# 1_interface.net
KiCad netlist of a schematic drawn in Altium Designer
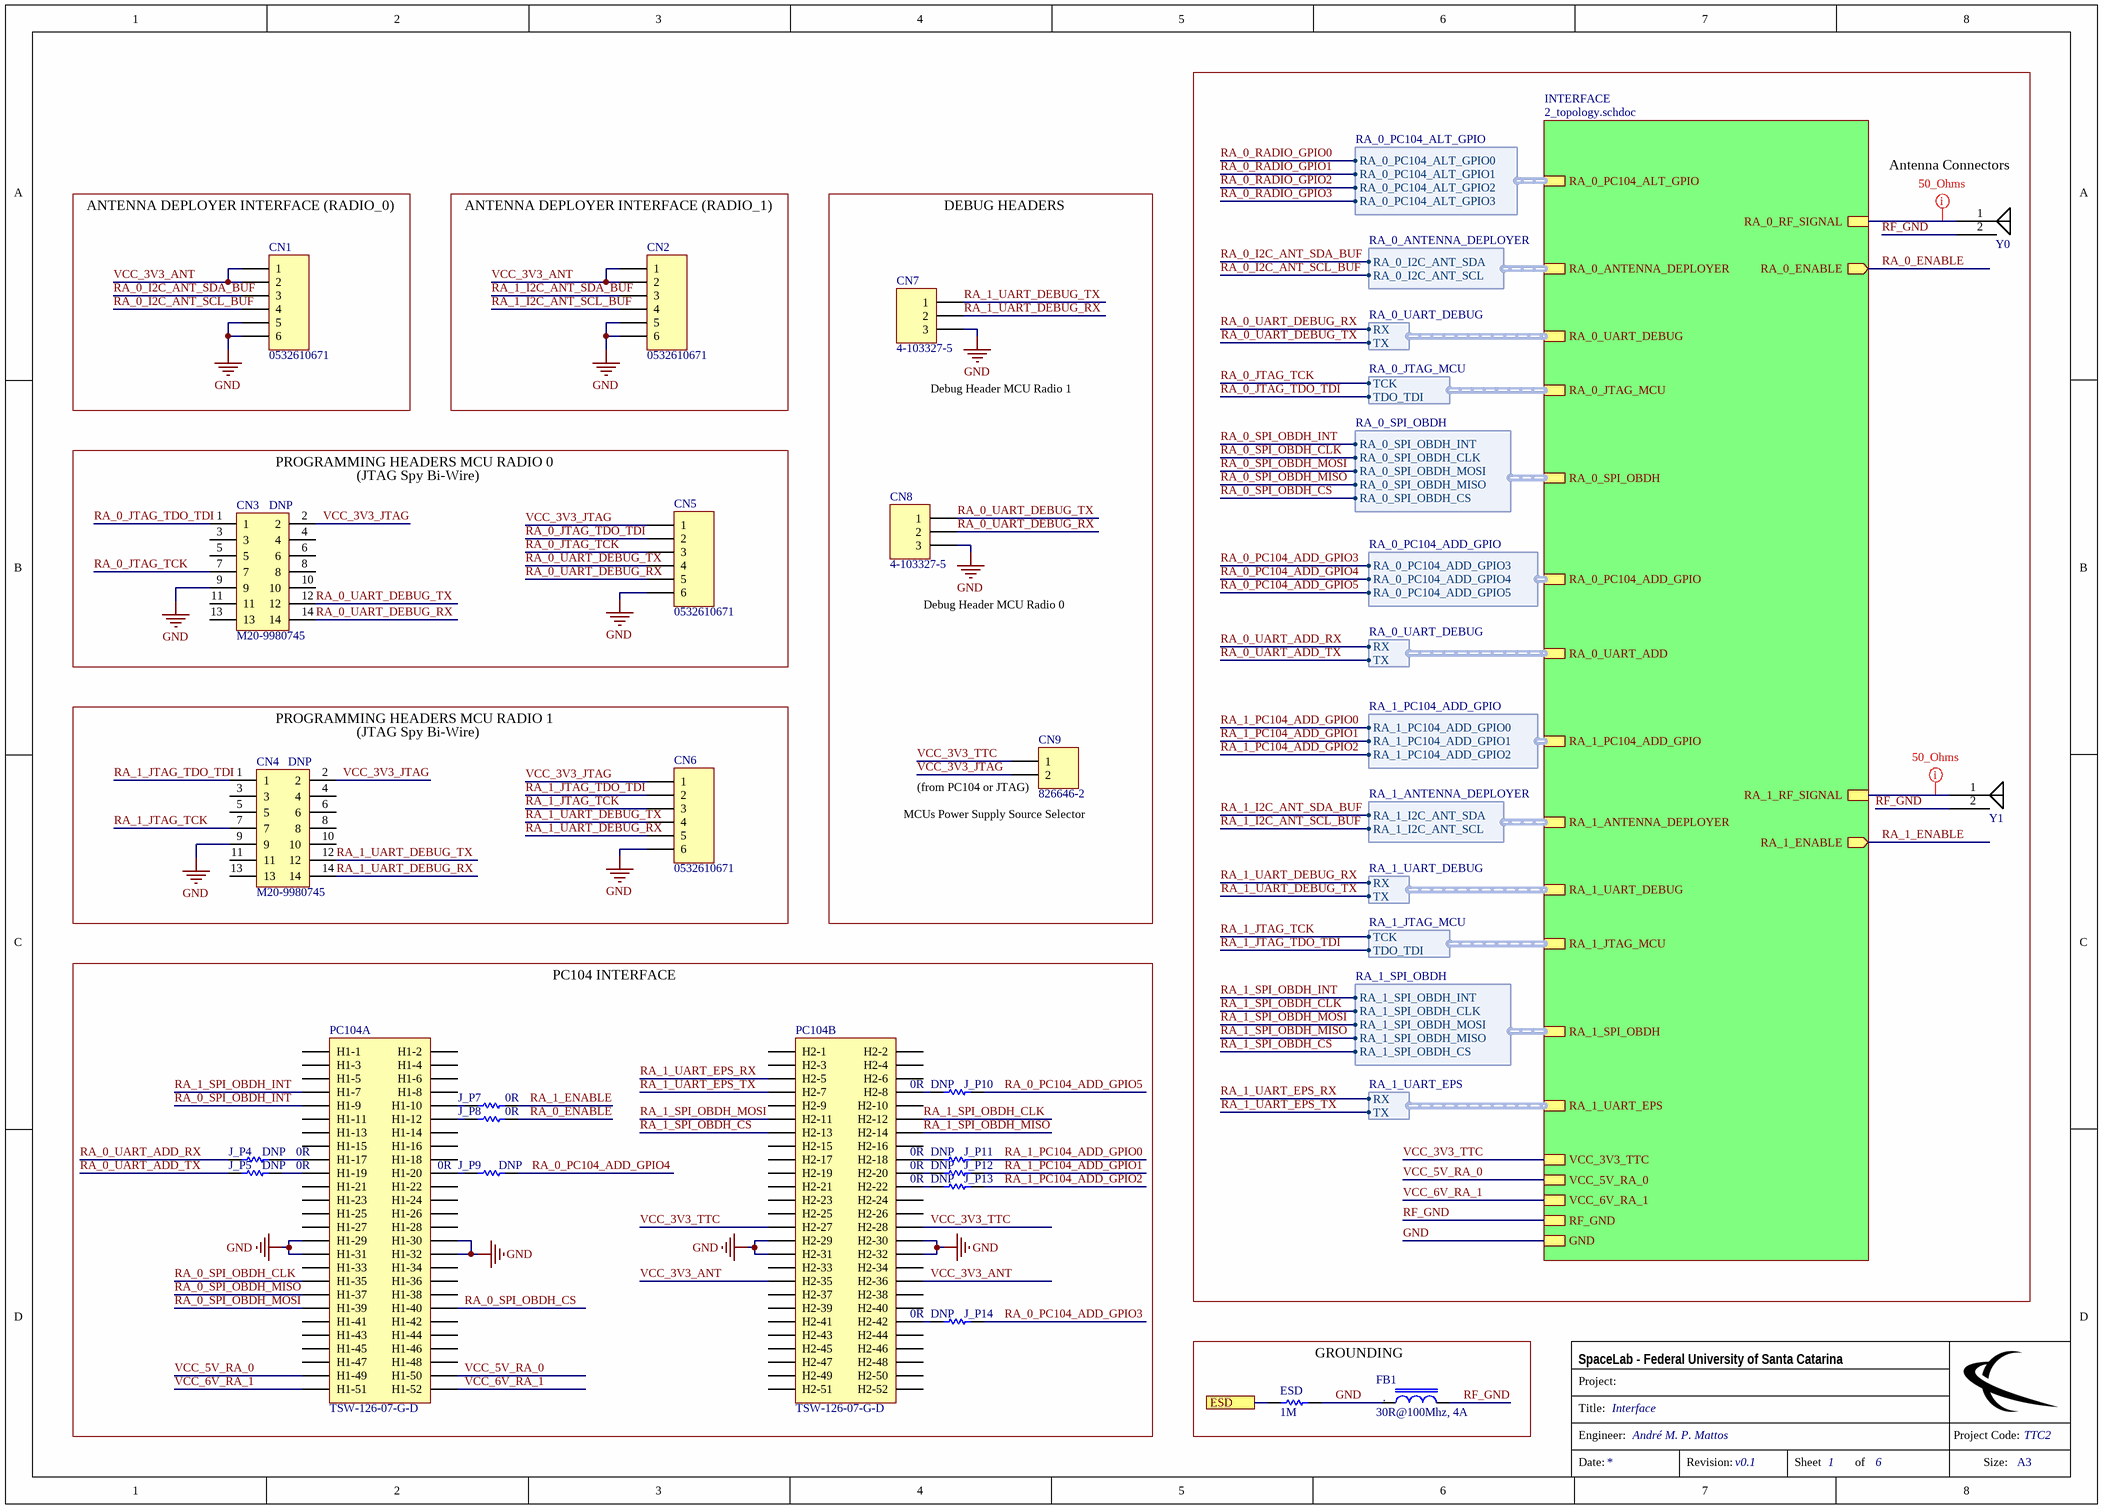
[diagram p0: 1_interface.schdoc]

(export (version "E")
  (design (tool "Eeschema 10.0.6"))
  (components
    (comp (ref "CN1")
      (value "0532610671")
      (footprint "PICOBLADE 6PIN Right Angle")
      (description "PicoBlade 6 Position Right Angle Connector Header Surface Mount  0.049\" (1.25mm)")
      (fields (field (name "PUBLISHER") "Altium Limited"))
      (libsource (lib "schematics_library_legacy") (part "0532610671"))
    )
    (comp (ref "CN2")
      (value "0532610671")
      (footprint "PICOBLADE 6PIN Right Angle")
      (description "PicoBlade 6 Position Right Angle Connector Header Surface Mount  0.049\" (1.25mm)")
      (fields (field (name "PUBLISHER") "Altium Limited"))
      (libsource (lib "schematics_library_legacy") (part "0532610671"))
    )
    (comp (ref "CN3")
      (value "M20-9980745")
      (footprint "CONN HEADER VERT 14POS 2.54MM")
      (description "Connector Header Through Hole 14 position 0.100\" (2.54mm)")
      (fields (field (name "MANUFACTURER") "Harwin"))
      (libsource (lib "schematics_library_legacy") (part "M20-9980745"))
    )
    (comp (ref "CN4")
      (value "M20-9980745")
      (footprint "CONN HEADER VERT 14POS 2.54MM")
      (description "Connector Header Through Hole 14 position 0.100\" (2.54mm)")
      (fields (field (name "MANUFACTURER") "Harwin"))
      (libsource (lib "schematics_library_legacy") (part "M20-9980745"))
    )
    (comp (ref "CN5")
      (value "0532610671")
      (footprint "PICOBLADE 6PIN Right Angle")
      (description "PicoBlade 6 Position Right Angle Connector Header Surface Mount  0.049\" (1.25mm)")
      (fields (field (name "PUBLISHER") "Altium Limited"))
      (libsource (lib "schematics_library_legacy") (part "0532610671"))
    )
    (comp (ref "CN6")
      (value "0532610671")
      (footprint "PICOBLADE 6PIN Right Angle")
      (description "PicoBlade 6 Position Right Angle Connector Header Surface Mount  0.049\" (1.25mm)")
      (fields (field (name "PUBLISHER") "Altium Limited"))
      (libsource (lib "schematics_library_legacy") (part "0532610671"))
    )
    (comp (ref "CN7")
      (value "4-103327-5")
      (footprint "HDR 1X3")
      (description "Connector Header Through Hole 3 position 0.100\" (2.54mm)")
      (fields (field (name "MANUFACTURER") "TE Connectivity AMP") (field (name "PUBLISHER") "Altium Limited"))
      (libsource (lib "schematics_library_legacy") (part "4-103327-5"))
    )
    (comp (ref "CN8")
      (value "4-103327-5")
      (footprint "HDR 1X3")
      (description "Connector Header Through Hole 3 position 0.100\" (2.54mm)")
      (fields (field (name "MANUFACTURER") "TE Connectivity AMP") (field (name "PUBLISHER") "Altium Limited"))
      (libsource (lib "schematics_library_legacy") (part "4-103327-5"))
    )
    (comp (ref "CN9")
      (value "826646-2")
      (footprint "HDR 1X2")
      (description "Connector Header Through Hole 2 position 0.100\" (2.54mm)")
      (fields (field (name "PUBLISHER") "Altium Limited"))
      (libsource (lib "schematics_library_legacy") (part "826646-2"))
    )
    (comp (ref "ESD")
      (value "1M")
      (footprint "0805")
      (description "RES 1000K OHM 1/8W 1% 0805")
      (fields (field (name "PARTNUMBER") "RMCF0805FG1M00"))
      (libsource (lib "schematics_library_legacy") (part "R1000k_1%_1/8W_0805"))
    )
    (comp (ref "FB1")
      (value "30R@100Mhz, 4A")
      (footprint "IND0805")
      (description "Ferrite Bead 30 OHM 4A 100MHz")
      (fields (field (name "PARTNUMBER") "BLM21PG300SN1D"))
      (libsource (lib "schematics_library_legacy") (part "FB_30R_4A_100MHz_0805"))
    )
    (comp (ref "J_P4")
      (value "0R")
      (footprint "0805")
      (description "RES 0R OHM 1/8W JUMPER 0805")
      (fields (field (name "PARTNUMBER") "CRCW08050000Z0EA"))
      (libsource (lib "schematics_library_legacy") (part "R0R_JUMPER_1/8W_0805"))
    )
    (comp (ref "J_P5")
      (value "0R")
      (footprint "0805")
      (description "RES 0R OHM 1/8W JUMPER 0805")
      (fields (field (name "PARTNUMBER") "CRCW08050000Z0EA"))
      (libsource (lib "schematics_library_legacy") (part "R0R_JUMPER_1/8W_0805"))
    )
    (comp (ref "J_P7")
      (value "0R")
      (footprint "0805")
      (description "RES 0R OHM 1/8W JUMPER 0805")
      (fields (field (name "PARTNUMBER") "CRCW08050000Z0EA"))
      (libsource (lib "schematics_library_legacy") (part "R0R_JUMPER_1/8W_0805"))
    )
    (comp (ref "J_P8")
      (value "0R")
      (footprint "0805")
      (description "RES 0R OHM 1/8W JUMPER 0805")
      (fields (field (name "PARTNUMBER") "CRCW08050000Z0EA"))
      (libsource (lib "schematics_library_legacy") (part "R0R_JUMPER_1/8W_0805"))
    )
    (comp (ref "J_P9")
      (value "0R")
      (footprint "0805")
      (description "RES 0R OHM 1/8W JUMPER 0805")
      (fields (field (name "PARTNUMBER") "CRCW08050000Z0EA"))
      (libsource (lib "schematics_library_legacy") (part "R0R_JUMPER_1/8W_0805"))
    )
    (comp (ref "J_P10")
      (value "0R")
      (footprint "0805")
      (description "RES 0R OHM 1/8W JUMPER 0805")
      (fields (field (name "PARTNUMBER") "CRCW08050000Z0EA"))
      (libsource (lib "schematics_library_legacy") (part "R0R_JUMPER_1/8W_0805"))
    )
    (comp (ref "J_P11")
      (value "0R")
      (footprint "0805")
      (description "RES 0R OHM 1/8W JUMPER 0805")
      (fields (field (name "PARTNUMBER") "CRCW08050000Z0EA"))
      (libsource (lib "schematics_library_legacy") (part "R0R_JUMPER_1/8W_0805"))
    )
    (comp (ref "J_P12")
      (value "0R")
      (footprint "0805")
      (description "RES 0R OHM 1/8W JUMPER 0805")
      (fields (field (name "PARTNUMBER") "CRCW08050000Z0EA"))
      (libsource (lib "schematics_library_legacy") (part "R0R_JUMPER_1/8W_0805"))
    )
    (comp (ref "J_P13")
      (value "0R")
      (footprint "0805")
      (description "RES 0R OHM 1/8W JUMPER 0805")
      (fields (field (name "PARTNUMBER") "CRCW08050000Z0EA"))
      (libsource (lib "schematics_library_legacy") (part "R0R_JUMPER_1/8W_0805"))
    )
    (comp (ref "J_P14")
      (value "0R")
      (footprint "0805")
      (description "RES 0R OHM 1/8W JUMPER 0805")
      (fields (field (name "PARTNUMBER") "CRCW08050000Z0EA"))
      (libsource (lib "schematics_library_legacy") (part "R0R_JUMPER_1/8W_0805"))
    )
    (comp (ref "PC104")
      (value "TSW-126-07-G-D")
      (footprint "PC104_TTC")
      (description "Connector Header Through Hole 52 position 0.100\" (2.54mm) - PC104 used in the TTC module")
      (fields (field (name "PARTNUMBER") "SSW-126-04-G-D"))
      (libsource (lib "schematics_library_legacy") (part "PC104_TTC"))
    )
    (comp (ref "Y0")
      (value "Coaxial_Connectors_90º")
      (footprint "CONN MCX JACK  R/A  50 OHM SMD")
      (description "MCX Connector Jack, Female Socket 50Ohm Through Hole, Right Angle Solder")
      (fields (field (name "PARTNUMBER") "133-3701-311"))
      (libsource (lib "schematics_library_legacy") (part "Coaxial_Connectors_90º"))
    )
    (comp (ref "Y1")
      (value "Coaxial_Connectors_90º")
      (footprint "CONN MCX JACK  R/A  50 OHM SMD")
      (description "MCX Connector Jack, Female Socket 50Ohm Through Hole, Right Angle Solder")
      (fields (field (name "PARTNUMBER") "133-3701-311"))
      (libsource (lib "schematics_library_legacy") (part "Coaxial_Connectors_90º"))
    )
  )
  (nets
    (net (code "13") (name "/ESD") (class "Default")
      (node (ref "ESD") (pin "2") (pinfunction "2_2") (pintype "passive"))
    )
    (net (code "14") (name "/RA_0_ENABLE") (class "Default")
      (node (ref "J_P8") (pin "1") (pinfunction "1_1") (pintype "passive"))
    )
    (net (code "15") (name "/RA_0_I2C_ANT_SCL_BUF") (class "Default")
      (node (ref "CN1") (pin "4") (pinfunction "4_4") (pintype "passive"))
    )
    (net (code "16") (name "/RA_0_I2C_ANT_SDA_BUF") (class "Default")
      (node (ref "CN1") (pin "3") (pinfunction "3_3") (pintype "passive"))
    )
    (net (code "17") (name "/RA_0_JTAG_TCK") (class "Default")
      (node (ref "CN3") (pin "7") (pinfunction "7_7") (pintype "passive"))
      (node (ref "CN5") (pin "3") (pinfunction "3_3") (pintype "passive"))
    )
    (net (code "18") (name "/RA_0_JTAG_TDO_TDI") (class "Default")
      (node (ref "CN3") (pin "1") (pinfunction "1_1") (pintype "passive"))
      (node (ref "CN5") (pin "2") (pinfunction "2_2") (pintype "passive"))
    )
    (net (code "19") (name "/RA_0_PC104_ADD_GPIO3") (class "Default")
      (node (ref "J_P14") (pin "1") (pinfunction "1_1") (pintype "passive"))
    )
    (net (code "20") (name "/RA_0_PC104_ADD_GPIO4") (class "Default")
      (node (ref "J_P9") (pin "1") (pinfunction "1_1") (pintype "passive"))
    )
    (net (code "21") (name "/RA_0_PC104_ADD_GPIO5") (class "Default")
      (node (ref "J_P10") (pin "1") (pinfunction "1_1") (pintype "passive"))
    )
    (net (code "26") (name "/RA_0_RF_SIGNAL") (class "Default")
      (node (ref "Y0") (pin "1") (pinfunction "1_1") (pintype "passive"))
    )
    (net (code "27") (name "/RA_0_SPI_OBDH_CLK") (class "Default")
      (node (ref "PC104") (pin "H1-35") (pinfunction "H1-35_H1-35") (pintype "passive"))
    )
    (net (code "28") (name "/RA_0_SPI_OBDH_CS") (class "Default")
      (node (ref "PC104") (pin "H1-40") (pinfunction "H1-40_H1-40") (pintype "passive"))
    )
    (net (code "29") (name "/RA_0_SPI_OBDH_INT") (class "Default")
      (node (ref "PC104") (pin "H1-9") (pinfunction "H1-9_H1-9") (pintype "passive"))
    )
    (net (code "30") (name "/RA_0_SPI_OBDH_MISO") (class "Default")
      (node (ref "PC104") (pin "H1-37") (pinfunction "H1-37_H1-37") (pintype "passive"))
    )
    (net (code "31") (name "/RA_0_SPI_OBDH_MOSI") (class "Default")
      (node (ref "PC104") (pin "H1-39") (pinfunction "H1-39_H1-39") (pintype "passive"))
    )
    (net (code "32") (name "/RA_0_UART_ADD_RX") (class "Default")
      (node (ref "J_P4") (pin "2") (pinfunction "2_2") (pintype "passive"))
    )
    (net (code "33") (name "/RA_0_UART_ADD_TX") (class "Default")
      (node (ref "J_P5") (pin "2") (pinfunction "2_2") (pintype "passive"))
    )
    (net (code "34") (name "/RA_0_UART_DEBUG_RX") (class "Default")
      (node (ref "CN3") (pin "14") (pinfunction "14_14") (pintype "passive"))
      (node (ref "CN5") (pin "5") (pinfunction "5_5") (pintype "passive"))
      (node (ref "CN8") (pin "2") (pinfunction "2_2") (pintype "passive"))
    )
    (net (code "35") (name "/RA_0_UART_DEBUG_TX") (class "Default")
      (node (ref "CN3") (pin "12") (pinfunction "12_12") (pintype "passive"))
      (node (ref "CN5") (pin "4") (pinfunction "4_4") (pintype "passive"))
      (node (ref "CN8") (pin "1") (pinfunction "1_1") (pintype "passive"))
    )
    (net (code "36") (name "/RA_1_ENABLE") (class "Default")
      (node (ref "J_P7") (pin "1") (pinfunction "1_1") (pintype "passive"))
    )
    (net (code "37") (name "/RA_1_I2C_ANT_SCL_BUF") (class "Default")
      (node (ref "CN2") (pin "4") (pinfunction "4_4") (pintype "passive"))
    )
    (net (code "38") (name "/RA_1_I2C_ANT_SDA_BUF") (class "Default")
      (node (ref "CN2") (pin "3") (pinfunction "3_3") (pintype "passive"))
    )
    (net (code "39") (name "/RA_1_JTAG_TCK") (class "Default")
      (node (ref "CN4") (pin "7") (pinfunction "7_7") (pintype "passive"))
      (node (ref "CN6") (pin "3") (pinfunction "3_3") (pintype "passive"))
    )
    (net (code "40") (name "/RA_1_JTAG_TDO_TDI") (class "Default")
      (node (ref "CN4") (pin "1") (pinfunction "1_1") (pintype "passive"))
      (node (ref "CN6") (pin "2") (pinfunction "2_2") (pintype "passive"))
    )
    (net (code "41") (name "/RA_1_PC104_ADD_GPIO0") (class "Default")
      (node (ref "J_P11") (pin "1") (pinfunction "1_1") (pintype "passive"))
    )
    (net (code "42") (name "/RA_1_PC104_ADD_GPIO1") (class "Default")
      (node (ref "J_P12") (pin "1") (pinfunction "1_1") (pintype "passive"))
    )
    (net (code "43") (name "/RA_1_PC104_ADD_GPIO2") (class "Default")
      (node (ref "J_P13") (pin "1") (pinfunction "1_1") (pintype "passive"))
    )
    (net (code "44") (name "/RA_1_RF_SIGNAL") (class "Default")
      (node (ref "Y1") (pin "1") (pinfunction "1_1") (pintype "passive"))
    )
    (net (code "45") (name "/RA_1_SPI_OBDH_CLK") (class "Default")
      (node (ref "PC104") (pin "H2-12") (pinfunction "H2-12_H2-12") (pintype "passive"))
    )
    (net (code "46") (name "/RA_1_SPI_OBDH_CS") (class "Default")
      (node (ref "PC104") (pin "H2-13") (pinfunction "H2-13_H2-13") (pintype "passive"))
    )
    (net (code "47") (name "/RA_1_SPI_OBDH_INT") (class "Default")
      (node (ref "PC104") (pin "H1-7") (pinfunction "H1-7_H1-7") (pintype "passive"))
    )
    (net (code "48") (name "/RA_1_SPI_OBDH_MISO") (class "Default")
      (node (ref "PC104") (pin "H2-14") (pinfunction "H2-14_H2-14") (pintype "passive"))
    )
    (net (code "49") (name "/RA_1_SPI_OBDH_MOSI") (class "Default")
      (node (ref "PC104") (pin "H2-11") (pinfunction "H2-11_H2-11") (pintype "passive"))
    )
    (net (code "50") (name "/RA_1_UART_DEBUG_RX") (class "Default")
      (node (ref "CN4") (pin "14") (pinfunction "14_14") (pintype "passive"))
      (node (ref "CN6") (pin "5") (pinfunction "5_5") (pintype "passive"))
      (node (ref "CN7") (pin "2") (pinfunction "2_2") (pintype "passive"))
    )
    (net (code "51") (name "/RA_1_UART_DEBUG_TX") (class "Default")
      (node (ref "CN4") (pin "12") (pinfunction "12_12") (pintype "passive"))
      (node (ref "CN6") (pin "4") (pinfunction "4_4") (pintype "passive"))
      (node (ref "CN7") (pin "1") (pinfunction "1_1") (pintype "passive"))
    )
    (net (code "52") (name "/RA_1_UART_EPS_RX") (class "Default")
      (node (ref "PC104") (pin "H2-5") (pinfunction "H2-5_H2-5") (pintype "passive"))
    )
    (net (code "53") (name "/RA_1_UART_EPS_TX") (class "Default")
      (node (ref "PC104") (pin "H2-7") (pinfunction "H2-7_H2-7") (pintype "passive"))
    )
    (net (code "54") (name "/RF_GND") (class "Default")
      (node (ref "FB1") (pin "2") (pinfunction "2_2") (pintype "passive"))
      (node (ref "Y0") (pin "2") (pinfunction "2_2") (pintype "passive"))
      (node (ref "Y1") (pin "2") (pinfunction "2_2") (pintype "passive"))
    )
    (net (code "55") (name "/VCC_3V3_ANT") (class "Default")
      (node (ref "CN1") (pin "1") (pinfunction "1_1") (pintype "passive"))
      (node (ref "CN1") (pin "2") (pinfunction "2_2") (pintype "passive"))
      (node (ref "CN2") (pin "1") (pinfunction "1_1") (pintype "passive"))
      (node (ref "CN2") (pin "2") (pinfunction "2_2") (pintype "passive"))
      (node (ref "PC104") (pin "H2-35") (pinfunction "H2-35_H2-35") (pintype "passive"))
      (node (ref "PC104") (pin "H2-36") (pinfunction "H2-36_H2-36") (pintype "passive"))
    )
    (net (code "56") (name "/VCC_3V3_JTAG") (class "Default")
      (node (ref "CN3") (pin "2") (pinfunction "2_2") (pintype "passive"))
      (node (ref "CN4") (pin "2") (pinfunction "2_2") (pintype "passive"))
      (node (ref "CN5") (pin "1") (pinfunction "1_1") (pintype "passive"))
      (node (ref "CN6") (pin "1") (pinfunction "1_1") (pintype "passive"))
      (node (ref "CN9") (pin "2") (pinfunction "2_2") (pintype "passive"))
    )
    (net (code "57") (name "/VCC_3V3_TTC") (class "Default")
      (node (ref "CN9") (pin "1") (pinfunction "1_1") (pintype "passive"))
      (node (ref "PC104") (pin "H2-27") (pinfunction "H2-27_H2-27") (pintype "passive"))
      (node (ref "PC104") (pin "H2-28") (pinfunction "H2-28_H2-28") (pintype "passive"))
    )
    (net (code "58") (name "/VCC_5V_RA_0") (class "Default")
      (node (ref "PC104") (pin "H1-49") (pinfunction "H1-49_H1-49") (pintype "passive"))
      (node (ref "PC104") (pin "H1-50") (pinfunction "H1-50_H1-50") (pintype "passive"))
    )
    (net (code "59") (name "/VCC_6V_RA_1") (class "Default")
      (node (ref "PC104") (pin "H1-51") (pinfunction "H1-51_H1-51") (pintype "passive"))
      (node (ref "PC104") (pin "H1-52") (pinfunction "H1-52_H1-52") (pintype "passive"))
    )
    (net (code "72") (name "GND") (class "Default")
      (node (ref "CN1") (pin "5") (pinfunction "5_5") (pintype "passive"))
      (node (ref "CN1") (pin "6") (pinfunction "6_6") (pintype "passive"))
      (node (ref "CN2") (pin "5") (pinfunction "5_5") (pintype "passive"))
      (node (ref "CN2") (pin "6") (pinfunction "6_6") (pintype "passive"))
      (node (ref "CN3") (pin "9") (pinfunction "9_9") (pintype "passive"))
      (node (ref "CN4") (pin "9") (pinfunction "9_9") (pintype "passive"))
      (node (ref "CN5") (pin "6") (pinfunction "6_6") (pintype "passive"))
      (node (ref "CN6") (pin "6") (pinfunction "6_6") (pintype "passive"))
      (node (ref "CN7") (pin "3") (pinfunction "3_3") (pintype "passive"))
      (node (ref "CN8") (pin "3") (pinfunction "3_3") (pintype "passive"))
      (node (ref "ESD") (pin "1") (pinfunction "1_1") (pintype "passive"))
      (node (ref "FB1") (pin "1") (pinfunction "1_1") (pintype "passive"))
      (node (ref "PC104") (pin "H1-29") (pinfunction "H1-29_H1-29") (pintype "passive"))
      (node (ref "PC104") (pin "H1-30") (pinfunction "H1-30_H1-30") (pintype "passive"))
      (node (ref "PC104") (pin "H1-31") (pinfunction "H1-31_H1-31") (pintype "passive"))
      (node (ref "PC104") (pin "H1-32") (pinfunction "H1-32_H1-32") (pintype "passive"))
      (node (ref "PC104") (pin "H2-29") (pinfunction "H2-29_H2-29") (pintype "passive"))
      (node (ref "PC104") (pin "H2-30") (pinfunction "H2-30_H2-30") (pintype "passive"))
      (node (ref "PC104") (pin "H2-31") (pinfunction "H2-31_H2-31") (pintype "passive"))
      (node (ref "PC104") (pin "H2-32") (pinfunction "H2-32_H2-32") (pintype "passive"))
    )
    (net (code "73") (name "Net-(J_P4-Pad1)") (class "Default")
      (node (ref "J_P4") (pin "1") (pinfunction "1_1") (pintype "passive"))
      (node (ref "PC104") (pin "H1-17") (pinfunction "H1-17_H1-17") (pintype "passive"))
    )
    (net (code "74") (name "Net-(J_P5-Pad1)") (class "Default")
      (node (ref "J_P5") (pin "1") (pinfunction "1_1") (pintype "passive"))
      (node (ref "PC104") (pin "H1-19") (pinfunction "H1-19_H1-19") (pintype "passive"))
    )
    (net (code "75") (name "Net-(J_P7-Pad2)") (class "Default")
      (node (ref "J_P7") (pin "2") (pinfunction "2_2") (pintype "passive"))
      (node (ref "PC104") (pin "H1-10") (pinfunction "H1-10_H1-10") (pintype "passive"))
    )
    (net (code "76") (name "Net-(J_P8-Pad2)") (class "Default")
      (node (ref "J_P8") (pin "2") (pinfunction "2_2") (pintype "passive"))
      (node (ref "PC104") (pin "H1-12") (pinfunction "H1-12_H1-12") (pintype "passive"))
    )
    (net (code "77") (name "Net-(J_P9-Pad2)") (class "Default")
      (node (ref "J_P9") (pin "2") (pinfunction "2_2") (pintype "passive"))
      (node (ref "PC104") (pin "H1-20") (pinfunction "H1-20_H1-20") (pintype "passive"))
    )
    (net (code "78") (name "Net-(J_P10-Pad2)") (class "Default")
      (node (ref "J_P10") (pin "2") (pinfunction "2_2") (pintype "passive"))
      (node (ref "PC104") (pin "H2-8") (pinfunction "H2-8_H2-8") (pintype "passive"))
    )
    (net (code "79") (name "Net-(J_P11-Pad2)") (class "Default")
      (node (ref "J_P11") (pin "2") (pinfunction "2_2") (pintype "passive"))
      (node (ref "PC104") (pin "H2-18") (pinfunction "H2-18_H2-18") (pintype "passive"))
    )
    (net (code "80") (name "Net-(J_P12-Pad2)") (class "Default")
      (node (ref "J_P12") (pin "2") (pinfunction "2_2") (pintype "passive"))
      (node (ref "PC104") (pin "H2-20") (pinfunction "H2-20_H2-20") (pintype "passive"))
    )
    (net (code "81") (name "Net-(J_P13-Pad2)") (class "Default")
      (node (ref "J_P13") (pin "2") (pinfunction "2_2") (pintype "passive"))
      (node (ref "PC104") (pin "H2-22") (pinfunction "H2-22_H2-22") (pintype "passive"))
    )
    (net (code "82") (name "Net-(J_P14-Pad2)") (class "Default")
      (node (ref "J_P14") (pin "2") (pinfunction "2_2") (pintype "passive"))
      (node (ref "PC104") (pin "H2-42") (pinfunction "H2-42_H2-42") (pintype "passive"))
    )
    (net (code "83") (name "unconnected-(CN3-Pad3)") (class "Default")
      (node (ref "CN3") (pin "3") (pinfunction "3_3") (pintype "passive"))
    )
    (net (code "84") (name "unconnected-(CN3-Pad4)") (class "Default")
      (node (ref "CN3") (pin "4") (pinfunction "4_4") (pintype "passive"))
    )
    (net (code "85") (name "unconnected-(CN3-Pad5)") (class "Default")
      (node (ref "CN3") (pin "5") (pinfunction "5_5") (pintype "passive"))
    )
    (net (code "86") (name "unconnected-(CN3-Pad6)") (class "Default")
      (node (ref "CN3") (pin "6") (pinfunction "6_6") (pintype "passive"))
    )
    (net (code "87") (name "unconnected-(CN3-Pad8)") (class "Default")
      (node (ref "CN3") (pin "8") (pinfunction "8_8") (pintype "passive"))
    )
    (net (code "88") (name "unconnected-(CN3-Pad10)") (class "Default")
      (node (ref "CN3") (pin "10") (pinfunction "10_10") (pintype "passive"))
    )
    (net (code "89") (name "unconnected-(CN3-Pad11)") (class "Default")
      (node (ref "CN3") (pin "11") (pinfunction "11_11") (pintype "passive"))
    )
    (net (code "90") (name "unconnected-(CN3-Pad13)") (class "Default")
      (node (ref "CN3") (pin "13") (pinfunction "13_13") (pintype "passive"))
    )
    (net (code "91") (name "unconnected-(CN4-Pad3)") (class "Default")
      (node (ref "CN4") (pin "3") (pinfunction "3_3") (pintype "passive"))
    )
    (net (code "92") (name "unconnected-(CN4-Pad4)") (class "Default")
      (node (ref "CN4") (pin "4") (pinfunction "4_4") (pintype "passive"))
    )
    (net (code "93") (name "unconnected-(CN4-Pad5)") (class "Default")
      (node (ref "CN4") (pin "5") (pinfunction "5_5") (pintype "passive"))
    )
    (net (code "94") (name "unconnected-(CN4-Pad6)") (class "Default")
      (node (ref "CN4") (pin "6") (pinfunction "6_6") (pintype "passive"))
    )
    (net (code "95") (name "unconnected-(CN4-Pad8)") (class "Default")
      (node (ref "CN4") (pin "8") (pinfunction "8_8") (pintype "passive"))
    )
    (net (code "96") (name "unconnected-(CN4-Pad10)") (class "Default")
      (node (ref "CN4") (pin "10") (pinfunction "10_10") (pintype "passive"))
    )
    (net (code "97") (name "unconnected-(CN4-Pad11)") (class "Default")
      (node (ref "CN4") (pin "11") (pinfunction "11_11") (pintype "passive"))
    )
    (net (code "98") (name "unconnected-(CN4-Pad13)") (class "Default")
      (node (ref "CN4") (pin "13") (pinfunction "13_13") (pintype "passive"))
    )
    (net (code "99") (name "unconnected-(PC104-PadH1-1)") (class "Default")
      (node (ref "PC104") (pin "H1-1") (pinfunction "H1-1_H1-1") (pintype "passive"))
    )
    (net (code "100") (name "unconnected-(PC104-PadH1-2)") (class "Default")
      (node (ref "PC104") (pin "H1-2") (pinfunction "H1-2_H1-2") (pintype "passive"))
    )
    (net (code "101") (name "unconnected-(PC104-PadH1-3)") (class "Default")
      (node (ref "PC104") (pin "H1-3") (pinfunction "H1-3_H1-3") (pintype "passive"))
    )
    (net (code "102") (name "unconnected-(PC104-PadH1-4)") (class "Default")
      (node (ref "PC104") (pin "H1-4") (pinfunction "H1-4_H1-4") (pintype "passive"))
    )
    (net (code "103") (name "unconnected-(PC104-PadH1-5)") (class "Default")
      (node (ref "PC104") (pin "H1-5") (pinfunction "H1-5_H1-5") (pintype "passive"))
    )
    (net (code "104") (name "unconnected-(PC104-PadH1-6)") (class "Default")
      (node (ref "PC104") (pin "H1-6") (pinfunction "H1-6_H1-6") (pintype "passive"))
    )
    (net (code "105") (name "unconnected-(PC104-PadH1-8)") (class "Default")
      (node (ref "PC104") (pin "H1-8") (pinfunction "H1-8_H1-8") (pintype "passive"))
    )
    (net (code "106") (name "unconnected-(PC104-PadH1-11)") (class "Default")
      (node (ref "PC104") (pin "H1-11") (pinfunction "H1-11_H1-11") (pintype "passive"))
    )
    (net (code "107") (name "unconnected-(PC104-PadH1-13)") (class "Default")
      (node (ref "PC104") (pin "H1-13") (pinfunction "H1-13_H1-13") (pintype "passive"))
    )
    (net (code "108") (name "unconnected-(PC104-PadH1-14)") (class "Default")
      (node (ref "PC104") (pin "H1-14") (pinfunction "H1-14_H1-14") (pintype "passive"))
    )
    (net (code "109") (name "unconnected-(PC104-PadH1-15)") (class "Default")
      (node (ref "PC104") (pin "H1-15") (pinfunction "H1-15_H1-15") (pintype "passive"))
    )
    (net (code "110") (name "unconnected-(PC104-PadH1-16)") (class "Default")
      (node (ref "PC104") (pin "H1-16") (pinfunction "H1-16_H1-16") (pintype "passive"))
    )
    (net (code "111") (name "unconnected-(PC104-PadH1-18)") (class "Default")
      (node (ref "PC104") (pin "H1-18") (pinfunction "H1-18_H1-18") (pintype "passive"))
    )
    (net (code "112") (name "unconnected-(PC104-PadH1-21)") (class "Default")
      (node (ref "PC104") (pin "H1-21") (pinfunction "H1-21_H1-21") (pintype "passive"))
    )
    (net (code "113") (name "unconnected-(PC104-PadH1-22)") (class "Default")
      (node (ref "PC104") (pin "H1-22") (pinfunction "H1-22_H1-22") (pintype "passive"))
    )
    (net (code "114") (name "unconnected-(PC104-PadH1-23)") (class "Default")
      (node (ref "PC104") (pin "H1-23") (pinfunction "H1-23_H1-23") (pintype "passive"))
    )
    (net (code "115") (name "unconnected-(PC104-PadH1-24)") (class "Default")
      (node (ref "PC104") (pin "H1-24") (pinfunction "H1-24_H1-24") (pintype "passive"))
    )
    (net (code "116") (name "unconnected-(PC104-PadH1-25)") (class "Default")
      (node (ref "PC104") (pin "H1-25") (pinfunction "H1-25_H1-25") (pintype "passive"))
    )
    (net (code "117") (name "unconnected-(PC104-PadH1-26)") (class "Default")
      (node (ref "PC104") (pin "H1-26") (pinfunction "H1-26_H1-26") (pintype "passive"))
    )
    (net (code "118") (name "unconnected-(PC104-PadH1-27)") (class "Default")
      (node (ref "PC104") (pin "H1-27") (pinfunction "H1-27_H1-27") (pintype "passive"))
    )
    (net (code "119") (name "unconnected-(PC104-PadH1-28)") (class "Default")
      (node (ref "PC104") (pin "H1-28") (pinfunction "H1-28_H1-28") (pintype "passive"))
    )
    (net (code "120") (name "unconnected-(PC104-PadH1-33)") (class "Default")
      (node (ref "PC104") (pin "H1-33") (pinfunction "H1-33_H1-33") (pintype "passive"))
    )
    (net (code "121") (name "unconnected-(PC104-PadH1-34)") (class "Default")
      (node (ref "PC104") (pin "H1-34") (pinfunction "H1-34_H1-34") (pintype "passive"))
    )
    (net (code "122") (name "unconnected-(PC104-PadH1-36)") (class "Default")
      (node (ref "PC104") (pin "H1-36") (pinfunction "H1-36_H1-36") (pintype "passive"))
    )
    (net (code "123") (name "unconnected-(PC104-PadH1-38)") (class "Default")
      (node (ref "PC104") (pin "H1-38") (pinfunction "H1-38_H1-38") (pintype "passive"))
    )
    (net (code "124") (name "unconnected-(PC104-PadH1-41)") (class "Default")
      (node (ref "PC104") (pin "H1-41") (pinfunction "H1-41_H1-41") (pintype "passive"))
    )
    (net (code "125") (name "unconnected-(PC104-PadH1-42)") (class "Default")
      (node (ref "PC104") (pin "H1-42") (pinfunction "H1-42_H1-42") (pintype "passive"))
    )
    (net (code "126") (name "unconnected-(PC104-PadH1-43)") (class "Default")
      (node (ref "PC104") (pin "H1-43") (pinfunction "H1-43_H1-43") (pintype "passive"))
    )
    (net (code "127") (name "unconnected-(PC104-PadH1-44)") (class "Default")
      (node (ref "PC104") (pin "H1-44") (pinfunction "H1-44_H1-44") (pintype "passive"))
    )
    (net (code "128") (name "unconnected-(PC104-PadH1-45)") (class "Default")
      (node (ref "PC104") (pin "H1-45") (pinfunction "H1-45_H1-45") (pintype "passive"))
    )
    (net (code "129") (name "unconnected-(PC104-PadH1-46)") (class "Default")
      (node (ref "PC104") (pin "H1-46") (pinfunction "H1-46_H1-46") (pintype "passive"))
    )
    (net (code "130") (name "unconnected-(PC104-PadH1-47)") (class "Default")
      (node (ref "PC104") (pin "H1-47") (pinfunction "H1-47_H1-47") (pintype "passive"))
    )
    (net (code "131") (name "unconnected-(PC104-PadH1-48)") (class "Default")
      (node (ref "PC104") (pin "H1-48") (pinfunction "H1-48_H1-48") (pintype "passive"))
    )
    (net (code "132") (name "unconnected-(PC104-PadH2-1)") (class "Default")
      (node (ref "PC104") (pin "H2-1") (pinfunction "H2-1_H2-1") (pintype "passive"))
    )
    (net (code "133") (name "unconnected-(PC104-PadH2-2)") (class "Default")
      (node (ref "PC104") (pin "H2-2") (pinfunction "H2-2_H2-2") (pintype "passive"))
    )
    (net (code "134") (name "unconnected-(PC104-PadH2-3)") (class "Default")
      (node (ref "PC104") (pin "H2-3") (pinfunction "H2-3_H2-3") (pintype "passive"))
    )
    (net (code "135") (name "unconnected-(PC104-PadH2-4)") (class "Default")
      (node (ref "PC104") (pin "H2-4") (pinfunction "H2-4_H2-4") (pintype "passive"))
    )
    (net (code "136") (name "unconnected-(PC104-PadH2-6)") (class "Default")
      (node (ref "PC104") (pin "H2-6") (pinfunction "H2-6_H2-6") (pintype "passive"))
    )
    (net (code "137") (name "unconnected-(PC104-PadH2-9)") (class "Default")
      (node (ref "PC104") (pin "H2-9") (pinfunction "H2-9_H2-9") (pintype "passive"))
    )
    (net (code "138") (name "unconnected-(PC104-PadH2-10)") (class "Default")
      (node (ref "PC104") (pin "H2-10") (pinfunction "H2-10_H2-10") (pintype "passive"))
    )
    (net (code "139") (name "unconnected-(PC104-PadH2-15)") (class "Default")
      (node (ref "PC104") (pin "H2-15") (pinfunction "H2-15_H2-15") (pintype "passive"))
    )
    (net (code "140") (name "unconnected-(PC104-PadH2-16)") (class "Default")
      (node (ref "PC104") (pin "H2-16") (pinfunction "H2-16_H2-16") (pintype "passive"))
    )
    (net (code "141") (name "unconnected-(PC104-PadH2-17)") (class "Default")
      (node (ref "PC104") (pin "H2-17") (pinfunction "H2-17_H2-17") (pintype "passive"))
    )
    (net (code "142") (name "unconnected-(PC104-PadH2-19)") (class "Default")
      (node (ref "PC104") (pin "H2-19") (pinfunction "H2-19_H2-19") (pintype "passive"))
    )
    (net (code "143") (name "unconnected-(PC104-PadH2-21)") (class "Default")
      (node (ref "PC104") (pin "H2-21") (pinfunction "H2-21_H2-21") (pintype "passive"))
    )
    (net (code "144") (name "unconnected-(PC104-PadH2-23)") (class "Default")
      (node (ref "PC104") (pin "H2-23") (pinfunction "H2-23_H2-23") (pintype "passive"))
    )
    (net (code "145") (name "unconnected-(PC104-PadH2-24)") (class "Default")
      (node (ref "PC104") (pin "H2-24") (pinfunction "H2-24_H2-24") (pintype "passive"))
    )
    (net (code "146") (name "unconnected-(PC104-PadH2-25)") (class "Default")
      (node (ref "PC104") (pin "H2-25") (pinfunction "H2-25_H2-25") (pintype "passive"))
    )
    (net (code "147") (name "unconnected-(PC104-PadH2-26)") (class "Default")
      (node (ref "PC104") (pin "H2-26") (pinfunction "H2-26_H2-26") (pintype "passive"))
    )
    (net (code "148") (name "unconnected-(PC104-PadH2-33)") (class "Default")
      (node (ref "PC104") (pin "H2-33") (pinfunction "H2-33_H2-33") (pintype "passive"))
    )
    (net (code "149") (name "unconnected-(PC104-PadH2-34)") (class "Default")
      (node (ref "PC104") (pin "H2-34") (pinfunction "H2-34_H2-34") (pintype "passive"))
    )
    (net (code "150") (name "unconnected-(PC104-PadH2-37)") (class "Default")
      (node (ref "PC104") (pin "H2-37") (pinfunction "H2-37_H2-37") (pintype "passive"))
    )
    (net (code "151") (name "unconnected-(PC104-PadH2-38)") (class "Default")
      (node (ref "PC104") (pin "H2-38") (pinfunction "H2-38_H2-38") (pintype "passive"))
    )
    (net (code "152") (name "unconnected-(PC104-PadH2-39)") (class "Default")
      (node (ref "PC104") (pin "H2-39") (pinfunction "H2-39_H2-39") (pintype "passive"))
    )
    (net (code "153") (name "unconnected-(PC104-PadH2-40)") (class "Default")
      (node (ref "PC104") (pin "H2-40") (pinfunction "H2-40_H2-40") (pintype "passive"))
    )
    (net (code "154") (name "unconnected-(PC104-PadH2-41)") (class "Default")
      (node (ref "PC104") (pin "H2-41") (pinfunction "H2-41_H2-41") (pintype "passive"))
    )
    (net (code "155") (name "unconnected-(PC104-PadH2-43)") (class "Default")
      (node (ref "PC104") (pin "H2-43") (pinfunction "H2-43_H2-43") (pintype "passive"))
    )
    (net (code "156") (name "unconnected-(PC104-PadH2-44)") (class "Default")
      (node (ref "PC104") (pin "H2-44") (pinfunction "H2-44_H2-44") (pintype "passive"))
    )
    (net (code "157") (name "unconnected-(PC104-PadH2-45)") (class "Default")
      (node (ref "PC104") (pin "H2-45") (pinfunction "H2-45_H2-45") (pintype "passive"))
    )
    (net (code "158") (name "unconnected-(PC104-PadH2-46)") (class "Default")
      (node (ref "PC104") (pin "H2-46") (pinfunction "H2-46_H2-46") (pintype "passive"))
    )
    (net (code "159") (name "unconnected-(PC104-PadH2-47)") (class "Default")
      (node (ref "PC104") (pin "H2-47") (pinfunction "H2-47_H2-47") (pintype "passive"))
    )
    (net (code "160") (name "unconnected-(PC104-PadH2-48)") (class "Default")
      (node (ref "PC104") (pin "H2-48") (pinfunction "H2-48_H2-48") (pintype "passive"))
    )
    (net (code "161") (name "unconnected-(PC104-PadH2-49)") (class "Default")
      (node (ref "PC104") (pin "H2-49") (pinfunction "H2-49_H2-49") (pintype "passive"))
    )
    (net (code "162") (name "unconnected-(PC104-PadH2-50)") (class "Default")
      (node (ref "PC104") (pin "H2-50") (pinfunction "H2-50_H2-50") (pintype "passive"))
    )
    (net (code "163") (name "unconnected-(PC104-PadH2-51)") (class "Default")
      (node (ref "PC104") (pin "H2-51") (pinfunction "H2-51_H2-51") (pintype "passive"))
    )
    (net (code "164") (name "unconnected-(PC104-PadH2-52)") (class "Default")
      (node (ref "PC104") (pin "H2-52") (pinfunction "H2-52_H2-52") (pintype "passive"))
    )
  )
)
